# Offset_Attenuator.net
KiCad netlist of a schematic drawn in Altium Designer
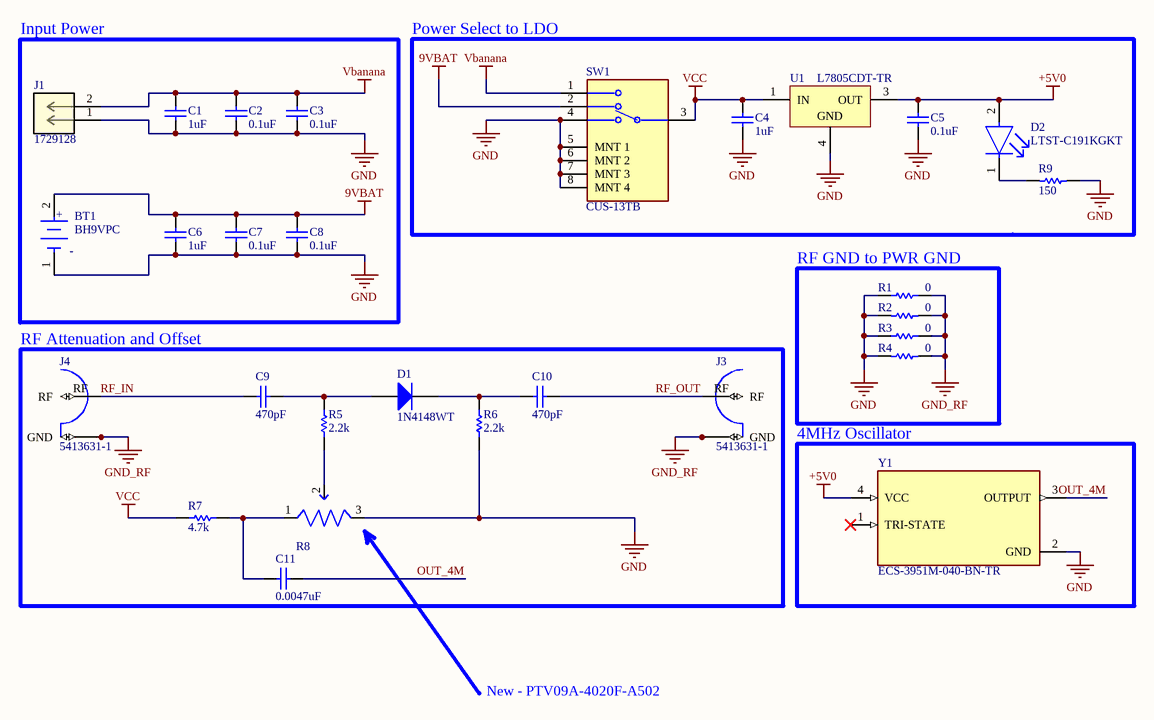
[diagram p0: Offset_Attenuator.SchDoc]

(export (version "E")
  (design (tool "Eeschema 10.0.6"))
  (components
    (comp (ref "BT1")
      (value "BH9VPC")
      (footprint "FP-BH9VPC-MFG")
      (description "Battery Holder (Open) 9V 1 Cell PC Pin")
      (fields (field (name "OCTOPART") "https://octopart.com/bh9vpc-memory+protection+devices-22788154"))
      (libsource (lib "Altium Content Vault") (part "60d3b5b901a8747834971d0eb8cf3fd"))
    )
    (comp (ref "C1")
      (value "1uF")
      (footprint "0603CAP")
      (description "0603 Ceramic Chip Capacitor - Standard")
      (fields (field (name "Comment") "C0603"))
      (libsource (lib "Standard Components") (part "C0603"))
    )
    (comp (ref "C2")
      (value "0.1uF")
      (footprint "0603CAP")
      (description "0603 Ceramic Chip Capacitor - Standard")
      (fields (field (name "Comment") "C0603"))
      (libsource (lib "Standard Components") (part "C0603"))
    )
    (comp (ref "C3")
      (value "0.1uF")
      (footprint "0603CAP")
      (description "0603 Ceramic Chip Capacitor - Standard")
      (fields (field (name "Comment") "C0603"))
      (libsource (lib "Standard Components") (part "C0603"))
    )
    (comp (ref "C4")
      (value "1uF")
      (footprint "0603CAP")
      (description "0603 Ceramic Chip Capacitor - Standard")
      (fields (field (name "Comment") "C0603"))
      (libsource (lib "Standard Components") (part "C0603"))
    )
    (comp (ref "C5")
      (value "0.1uF")
      (footprint "0603CAP")
      (description "0603 Ceramic Chip Capacitor - Standard")
      (fields (field (name "Comment") "C0603"))
      (libsource (lib "Standard Components") (part "C0603"))
    )
    (comp (ref "C6")
      (value "1uF")
      (footprint "0603CAP")
      (description "0603 Ceramic Chip Capacitor - Standard")
      (fields (field (name "Comment") "C0603"))
      (libsource (lib "Standard Components") (part "C0603"))
    )
    (comp (ref "C7")
      (value "0.1uF")
      (footprint "0603CAP")
      (description "0603 Ceramic Chip Capacitor - Standard")
      (fields (field (name "Comment") "C0603"))
      (libsource (lib "Standard Components") (part "C0603"))
    )
    (comp (ref "C8")
      (value "0.1uF")
      (footprint "0603CAP")
      (description "0603 Ceramic Chip Capacitor - Standard")
      (fields (field (name "Comment") "C0603"))
      (libsource (lib "Standard Components") (part "C0603"))
    )
    (comp (ref "C9")
      (value "470pF")
      (footprint "0402cap")
      (description "0402 Ceramic Chip Capacitor - Standard")
      (fields (field (name "Comment") "C0402"))
      (libsource (lib "Standard Components") (part "C0402"))
    )
    (comp (ref "C10")
      (value "470pF")
      (footprint "0402cap")
      (description "0402 Ceramic Chip Capacitor - Standard")
      (fields (field (name "Comment") "C0402"))
      (libsource (lib "Standard Components") (part "C0402"))
    )
    (comp (ref "C11")
      (value "0.0047uF")
      (footprint "0603CAP")
      (description "0603 Ceramic Chip Capacitor - Standard")
      (fields (field (name "Comment") "C0603"))
      (libsource (lib "Standard Components") (part "C0603"))
    )
    (comp (ref "D1")
      (value "1N4148WT")
      (footprint "FAIR-SOD-523F-2_V")
      (description "High Conductance Fast Switching Diode, 75 V, -55 to 150 degC, 2-Pin SOD523F, RoHS")
      (fields (field (name "MANUFACTURER") "Fairchild Semiconductor"))
      (libsource (lib "Altium Content Vault") (part "FAIR-D_K1A2-2"))
    )
    (comp (ref "D2")
      (value "LTST-C191KGKT")
      (footprint "FP-LTST-C191KGKT-MFG")
      (description "LED GREEN CLEAR SMD")
      (libsource (lib "Altium Content Vault") (part "8706943c75ba83719d021d2fdc84c58"))
    )
    (comp (ref "J1")
      (value "1729128")
      (footprint "PHOE-1729128-2_V")
      (description "Block, Terminal; 13.5 A; 250 V; 5.08 mm; 26 to 16 AWG; 2; Screw; Solder; 4 kV")
      (libsource (lib "E3 Compliance LLC") (part "New symbol 1"))
    )
    (comp (ref "J3")
      (value "5413631-1")
      (footprint "5413631-1")
      (description "Nickel Plating 50 Ohm Right Angle Metalized Jack PCB BNC Connector")
      (fields (field (name "MF") "TE Connectivity"))
      (libsource (lib "") (part "5413631-1_1"))
    )
    (comp (ref "J4")
      (value "5413631-1")
      (footprint "5413631-1")
      (description "Nickel Plating 50 Ohm Right Angle Metalized Jack PCB BNC Connector")
      (fields (field (name "MF") "TE Connectivity"))
      (libsource (lib "5413631-1") (part "5413631-1"))
    )
    (comp (ref "R1")
      (value "0")
      (footprint "0805RES")
      (description "0805 Chip Resistor - Standard")
      (fields (field (name "Comment") "R0805"))
      (libsource (lib "Standard Components") (part "R0805"))
    )
    (comp (ref "R2")
      (value "0")
      (footprint "0805RES")
      (description "0805 Chip Resistor - Standard")
      (fields (field (name "Comment") "R0805"))
      (libsource (lib "Standard Components") (part "R0805"))
    )
    (comp (ref "R3")
      (value "0")
      (footprint "0805RES")
      (description "0805 Chip Resistor - Standard")
      (fields (field (name "Comment") "R0805"))
      (libsource (lib "Standard Components") (part "R0805"))
    )
    (comp (ref "R4")
      (value "0")
      (footprint "0805RES")
      (description "0805 Chip Resistor - Standard")
      (fields (field (name "Comment") "R0805"))
      (libsource (lib "Standard Components") (part "R0805"))
    )
    (comp (ref "R5")
      (value "Resistor 0R +/- 5% 1206 250 mW")
      (footprint "RESC3216X60X45ML15T20")
      (description "Chip Resistor, 0 Ohm, +/- 5%, 0.25 W, -55 to 155 degC, 1206 (3216 Metric)")
      (fields
        (field (name "TOLERANCE") "5%")
        (field (name "CR1206F2K20P05Z") "2.2k")
        (field (name "POWER") "250mW")
      )
      (libsource (lib "E3 Compliance LLC") (part "RES-2"))
    )
    (comp (ref "R6")
      (value "Resistor 0R +/- 5% 1206 250 mW")
      (footprint "RESC3216X60X45ML15T20")
      (description "Chip Resistor, 0 Ohm, +/- 5%, 0.25 W, -55 to 155 degC, 1206 (3216 Metric)")
      (fields
        (field (name "TOLERANCE") "5%")
        (field (name "CR1206F2K20P05Z") "2.2k")
        (field (name "POWER") "250mW")
      )
      (libsource (lib "E3 Compliance LLC") (part "RES-2"))
    )
    (comp (ref "R7")
      (value "Resistor 0R +/- 5% 1206 250 mW")
      (footprint "RESC3216X60X45ML15T20")
      (description "Chip Resistor, 0 Ohm, +/- 5%, 0.25 W, -55 to 155 degC, 1206 (3216 Metric)")
      (fields
        (field (name "TOLERANCE") "5%")
        (field (name "RMC12064.7K5%N") "4.7k")
        (field (name "POWER") "250mW")
      )
      (libsource (lib "E3 Compliance LLC") (part "RES-2"))
    )
    (comp (ref "R8")
      (value "EVU-F2LFL3D53")
      (footprint "EVU-F2LFL3D53")
      (libsource (lib "ProjectMainLib") (part "EVU-F2LFL3D53"))
    )
    (comp (ref "R9")
      (value "150")
      (footprint "0603RES")
      (description "0603 Chip Resistor - Standard")
      (fields (field (name "Comment") "R0603"))
      (libsource (lib "Standard Components") (part "R0603"))
    )
    (comp (ref "SW1")
      (value "CUS-13TB")
      (footprint "FP-CUS-13TB-MFG")
      (description "SWITCH SLIDE SP3T 300MA 4V")
      (libsource (lib "Altium Content Vault") (part "47bcb96ef67674530f45e4053201745"))
    )
    (comp (ref "U1")
      (value "L7805CDT-TR")
      (footprint "TO-252_N")
      (description "Positive Voltage Regulator, 3-Pin DPAK, Tape and Reel")
      (libsource (lib "Altium Content Vault") (part "PM-REG-L4940-SOT3"))
    )
    (comp (ref "Y1")
      (value "ECS-3951M-040-BN-TR")
      (footprint "OSC_ECS-3951M-040-BN-TR")
      (description "SMD CLOCK OSCILLATOR")
      (libsource (lib "ECS-3951M-040-BN-TR") (part "ECS-3951M-040-BN-TR"))
    )
  )
  (nets
    (net (code "1") (name "+5V0") (class "Default")
      (node (ref "C5") (pin "2") (pinfunction "2_2") (pintype "passive"))
      (node (ref "D2") (pin "2") (pinfunction "A_2") (pintype "passive"))
      (node (ref "U1") (pin "3") (pinfunction "OUT_3") (pintype "power_in"))
      (node (ref "Y1") (pin "4") (pinfunction "VCC_4") (pintype "input"))
    )
    (net (code "2") (name "/OUT_4M") (class "Default")
      (node (ref "C11") (pin "2") (pinfunction "2_2") (pintype "passive"))
      (node (ref "Y1") (pin "3") (pinfunction "OUTPUT_3") (pintype "output"))
    )
    (net (code "3") (name "/RF_IN") (class "Default")
      (node (ref "C9") (pin "1") (pinfunction "1_1") (pintype "passive"))
      (node (ref "J4") (pin "RF") (pinfunction "RF_RF") (pintype "bidirectional"))
    )
    (net (code "4") (name "/RF_OUT") (class "Default")
      (node (ref "C10") (pin "2") (pinfunction "2_2") (pintype "passive"))
      (node (ref "J3") (pin "RF") (pinfunction "RF_RF") (pintype "bidirectional"))
    )
    (net (code "5") (name "9VBAT") (class "Default")
      (node (ref "BT1") (pin "2") (pinfunction "A_2") (pintype "passive"))
      (node (ref "C6") (pin "2") (pinfunction "2_2") (pintype "passive"))
      (node (ref "C7") (pin "2") (pinfunction "2_2") (pintype "passive"))
      (node (ref "C8") (pin "2") (pinfunction "2_2") (pintype "passive"))
      (node (ref "SW1") (pin "2") (pinfunction "2_2") (pintype "passive"))
    )
    (net (code "6") (name "GND") (class "Default")
      (node (ref "BT1") (pin "1") (pinfunction "C_1") (pintype "passive"))
      (node (ref "C1") (pin "1") (pinfunction "1_1") (pintype "passive"))
      (node (ref "C2") (pin "1") (pinfunction "1_1") (pintype "passive"))
      (node (ref "C3") (pin "1") (pinfunction "1_1") (pintype "passive"))
      (node (ref "C4") (pin "1") (pinfunction "1_1") (pintype "passive"))
      (node (ref "C5") (pin "1") (pinfunction "1_1") (pintype "passive"))
      (node (ref "C6") (pin "1") (pinfunction "1_1") (pintype "passive"))
      (node (ref "C7") (pin "1") (pinfunction "1_1") (pintype "passive"))
      (node (ref "C8") (pin "1") (pinfunction "1_1") (pintype "passive"))
      (node (ref "J1") (pin "1") (pinfunction "1_1") (pintype "passive"))
      (node (ref "R1") (pin "1") (pinfunction "1_1") (pintype "passive"))
      (node (ref "R2") (pin "1") (pinfunction "1_1") (pintype "passive"))
      (node (ref "R3") (pin "1") (pinfunction "1_1") (pintype "passive"))
      (node (ref "R4") (pin "1") (pinfunction "1_1") (pintype "passive"))
      (node (ref "R6") (pin "1") (pinfunction "1_1") (pintype "passive"))
      (node (ref "R8") (pin "3") (pinfunction "3_3") (pintype "passive"))
      (node (ref "R9") (pin "2") (pinfunction "2_2") (pintype "passive"))
      (node (ref "SW1") (pin "4") (pinfunction "4_4") (pintype "passive"))
      (node (ref "SW1") (pin "5") (pinfunction "MNT_1_5") (pintype "passive"))
      (node (ref "SW1") (pin "6") (pinfunction "MNT_2_6") (pintype "passive"))
      (node (ref "SW1") (pin "7") (pinfunction "MNT_3_7") (pintype "passive"))
      (node (ref "SW1") (pin "8") (pinfunction "MNT_4_8") (pintype "passive"))
      (node (ref "U1") (pin "4") (pinfunction "GND_4") (pintype "power_in"))
      (node (ref "Y1") (pin "2") (pinfunction "GND_2") (pintype "power_in"))
    )
    (net (code "7") (name "GND_RF") (class "Default")
      (node (ref "J3") (pin "G1") (pinfunction "GND_G1") (pintype "bidirectional"))
      (node (ref "J3") (pin "G2") (pinfunction "GND_G2") (pintype "bidirectional"))
      (node (ref "J3") (pin "G3") (pinfunction "GND_G3") (pintype "bidirectional"))
      (node (ref "J3") (pin "G4") (pinfunction "GND_G4") (pintype "bidirectional"))
      (node (ref "J4") (pin "G1") (pinfunction "GND_G1") (pintype "bidirectional"))
      (node (ref "J4") (pin "G2") (pinfunction "GND_G2") (pintype "bidirectional"))
      (node (ref "J4") (pin "G3") (pinfunction "GND_G3") (pintype "bidirectional"))
      (node (ref "J4") (pin "G4") (pinfunction "GND_G4") (pintype "bidirectional"))
      (node (ref "R1") (pin "2") (pinfunction "2_2") (pintype "passive"))
      (node (ref "R2") (pin "2") (pinfunction "2_2") (pintype "passive"))
      (node (ref "R3") (pin "2") (pinfunction "2_2") (pintype "passive"))
      (node (ref "R4") (pin "2") (pinfunction "2_2") (pintype "passive"))
    )
    (net (code "8") (name "Net-(C11-Pad1)") (class "Default")
      (node (ref "C11") (pin "1") (pinfunction "1_1") (pintype "passive"))
      (node (ref "R7") (pin "1") (pinfunction "1_1") (pintype "passive"))
      (node (ref "R8") (pin "1") (pinfunction "1_1") (pintype "passive"))
    )
    (net (code "9") (name "Net-(D1-A)") (class "Default")
      (node (ref "C9") (pin "2") (pinfunction "2_2") (pintype "passive"))
      (node (ref "D1") (pin "2") (pinfunction "A_2") (pintype "passive"))
      (node (ref "R5") (pin "2") (pinfunction "2_2") (pintype "passive"))
    )
    (net (code "10") (name "Net-(D1-K)") (class "Default")
      (node (ref "C10") (pin "1") (pinfunction "1_1") (pintype "passive"))
      (node (ref "D1") (pin "1") (pinfunction "K_1") (pintype "passive"))
      (node (ref "R6") (pin "2") (pinfunction "2_2") (pintype "passive"))
    )
    (net (code "11") (name "Net-(D2-C)") (class "Default")
      (node (ref "D2") (pin "1") (pinfunction "C_1") (pintype "passive"))
      (node (ref "R9") (pin "1") (pinfunction "1_1") (pintype "passive"))
    )
    (net (code "12") (name "Net-(R5-Pad1)") (class "Default")
      (node (ref "R5") (pin "1") (pinfunction "1_1") (pintype "passive"))
      (node (ref "R8") (pin "2") (pinfunction "2_2") (pintype "passive"))
    )
    (net (code "13") (name "VCC") (class "Default")
      (node (ref "C4") (pin "2") (pinfunction "2_2") (pintype "passive"))
      (node (ref "R7") (pin "2") (pinfunction "2_2") (pintype "passive"))
      (node (ref "SW1") (pin "3") (pinfunction "C_3") (pintype "passive"))
      (node (ref "U1") (pin "1") (pinfunction "IN_1") (pintype "power_in"))
    )
    (net (code "14") (name "Vbanana") (class "Default")
      (node (ref "C1") (pin "2") (pinfunction "2_2") (pintype "passive"))
      (node (ref "C2") (pin "2") (pinfunction "2_2") (pintype "passive"))
      (node (ref "C3") (pin "2") (pinfunction "2_2") (pintype "passive"))
      (node (ref "J1") (pin "2") (pinfunction "2_2") (pintype "passive"))
      (node (ref "SW1") (pin "1") (pinfunction "1_1") (pintype "passive"))
    )
    (net (code "15") (name "unconnected-(Y1-TRI-STATE-Pad1)") (class "Default")
      (node (ref "Y1") (pin "1") (pinfunction "TRI-STATE_1") (pintype "input+no_connect"))
    )
  )
)
